# Thermocouple_Amplifier.net
KiCad netlist of a schematic drawn in Altium Designer
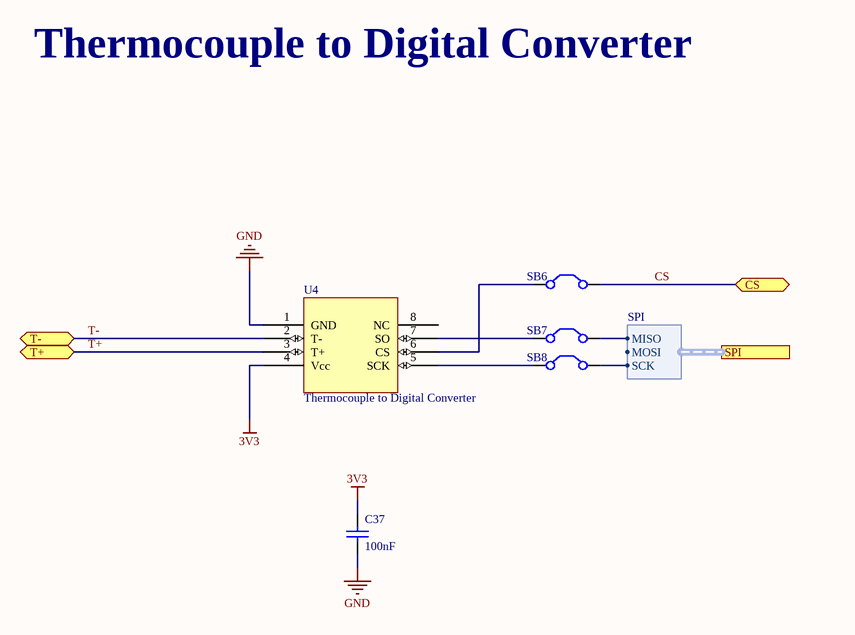
[diagram p0: Thermocouple_Amplifier.SchDoc]

(export (version "E")
  (design (tool "Eeschema 10.0.6"))
  (components
    (comp (ref "C37")
      (value "100nF")
      (footprint "0402")
      (description "Capacitor")
      (fields (field (name "Comment") "Cap"))
      (libsource (lib "Miscellaneous Devices") (part "Cap"))
    )
    (comp (ref "SB6")
      (value "Solder Bridge")
      (footprint "SB-2pos")
      (description "Jumper Wire")
      (libsource (lib "Miscellaneous Devices") (part "Jumper"))
    )
    (comp (ref "SB7")
      (value "Solder Bridge")
      (footprint "SB-2pos")
      (description "Jumper Wire")
      (libsource (lib "Miscellaneous Devices") (part "Jumper"))
    )
    (comp (ref "SB8")
      (value "Solder Bridge")
      (footprint "SB-2pos")
      (description "Jumper Wire")
      (libsource (lib "Miscellaneous Devices") (part "Jumper"))
    )
    (comp (ref "U4")
      (value "Thermocouple to Digital Converter")
      (footprint "8-SOIC MAXIM")
      (libsource (lib "LaunchyRIOComponents") (part "MAX31855x"))
    )
  )
  (nets
    (net (code "2") (name "/CS") (class "Default")
      (node (ref "SB6") (pin "2") (pinfunction "C2_2") (pintype "passive"))
    )
    (net (code "3") (name "/MISO") (class "Default")
      (node (ref "SB7") (pin "2") (pinfunction "C2_2") (pintype "passive"))
    )
    (net (code "4") (name "/SCK") (class "Default")
      (node (ref "SB8") (pin "2") (pinfunction "C2_2") (pintype "passive"))
    )
    (net (code "5") (name "/T+") (class "Default")
      (node (ref "U4") (pin "3") (pinfunction "T+_3") (pintype "bidirectional"))
    )
    (net (code "6") (name "/T-") (class "Default")
      (node (ref "U4") (pin "2") (pinfunction "T-_2") (pintype "bidirectional"))
    )
    (net (code "8") (name "3V3") (class "Default")
      (node (ref "C37") (pin "2") (pinfunction "2_2") (pintype "passive"))
      (node (ref "U4") (pin "4") (pinfunction "Vcc_4") (pintype "power_in"))
    )
    (net (code "9") (name "GND") (class "Default")
      (node (ref "C37") (pin "1") (pinfunction "1_1") (pintype "passive"))
      (node (ref "U4") (pin "1") (pinfunction "GND_1") (pintype "power_in"))
    )
    (net (code "10") (name "Net-(SB6-C1)") (class "Default")
      (node (ref "SB6") (pin "1") (pinfunction "C1_1") (pintype "passive"))
      (node (ref "U4") (pin "6") (pinfunction "CS_6") (pintype "bidirectional"))
    )
    (net (code "11") (name "Net-(SB7-C1)") (class "Default")
      (node (ref "SB7") (pin "1") (pinfunction "C1_1") (pintype "passive"))
      (node (ref "U4") (pin "7") (pinfunction "SO_7") (pintype "bidirectional"))
    )
    (net (code "12") (name "Net-(SB8-C1)") (class "Default")
      (node (ref "SB8") (pin "1") (pinfunction "C1_1") (pintype "passive"))
      (node (ref "U4") (pin "5") (pinfunction "SCK_5") (pintype "bidirectional"))
    )
    (net (code "13") (name "unconnected-(U4-NC-Pad8)") (class "Default")
      (node (ref "U4") (pin "8") (pinfunction "NC_8") (pintype "passive"))
    )
  )
)
